# Lipo_Rider_Plus.net
KiCad netlist of a schematic drawn in EAGLE
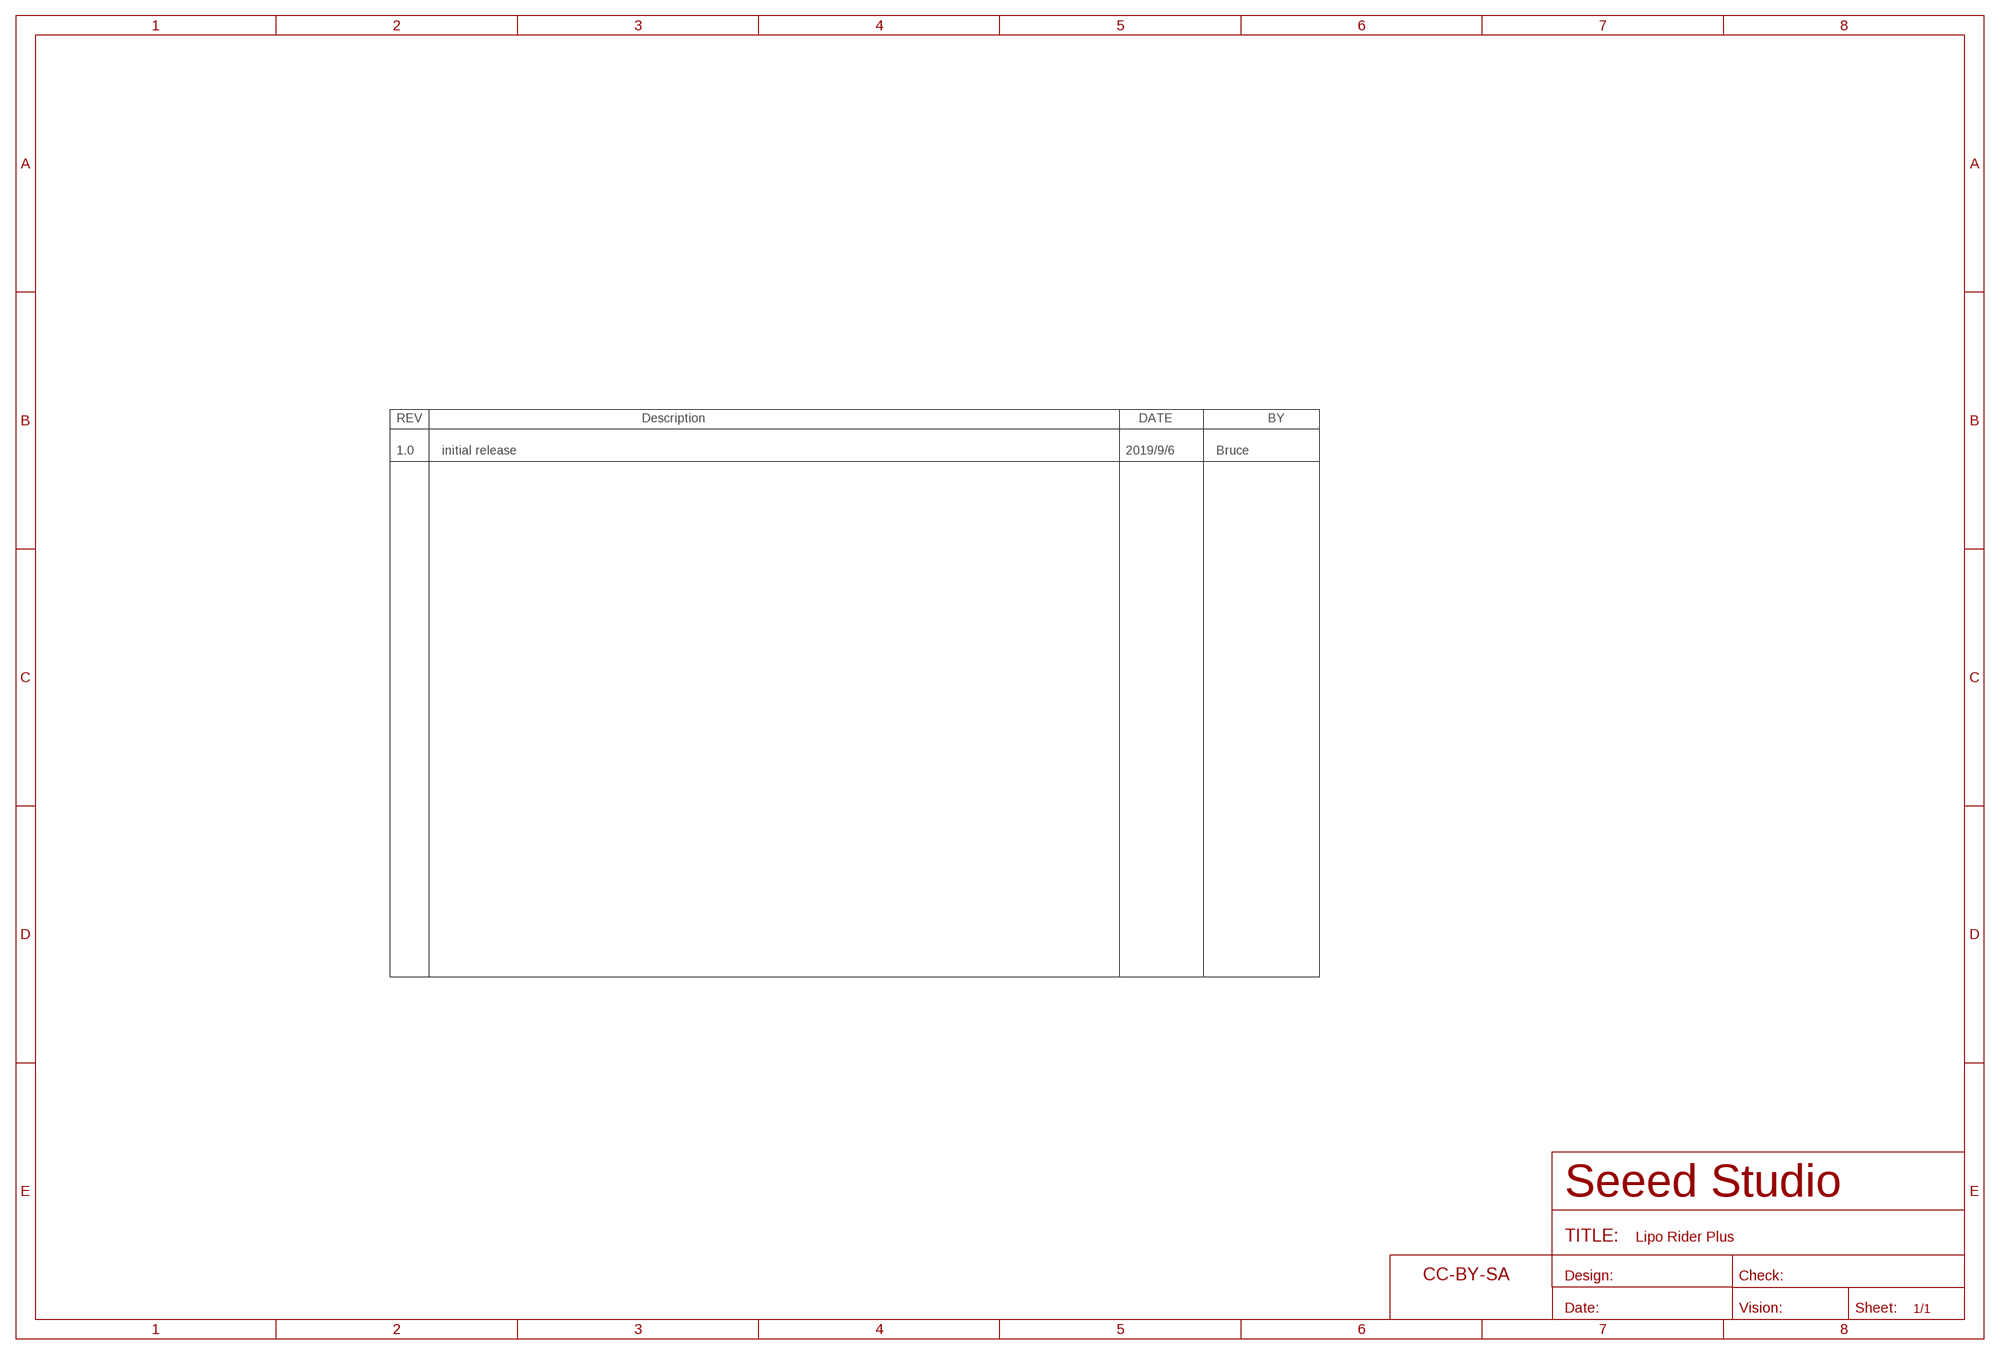
[diagram p0: schematic, sheet 1, part 1 of 2]
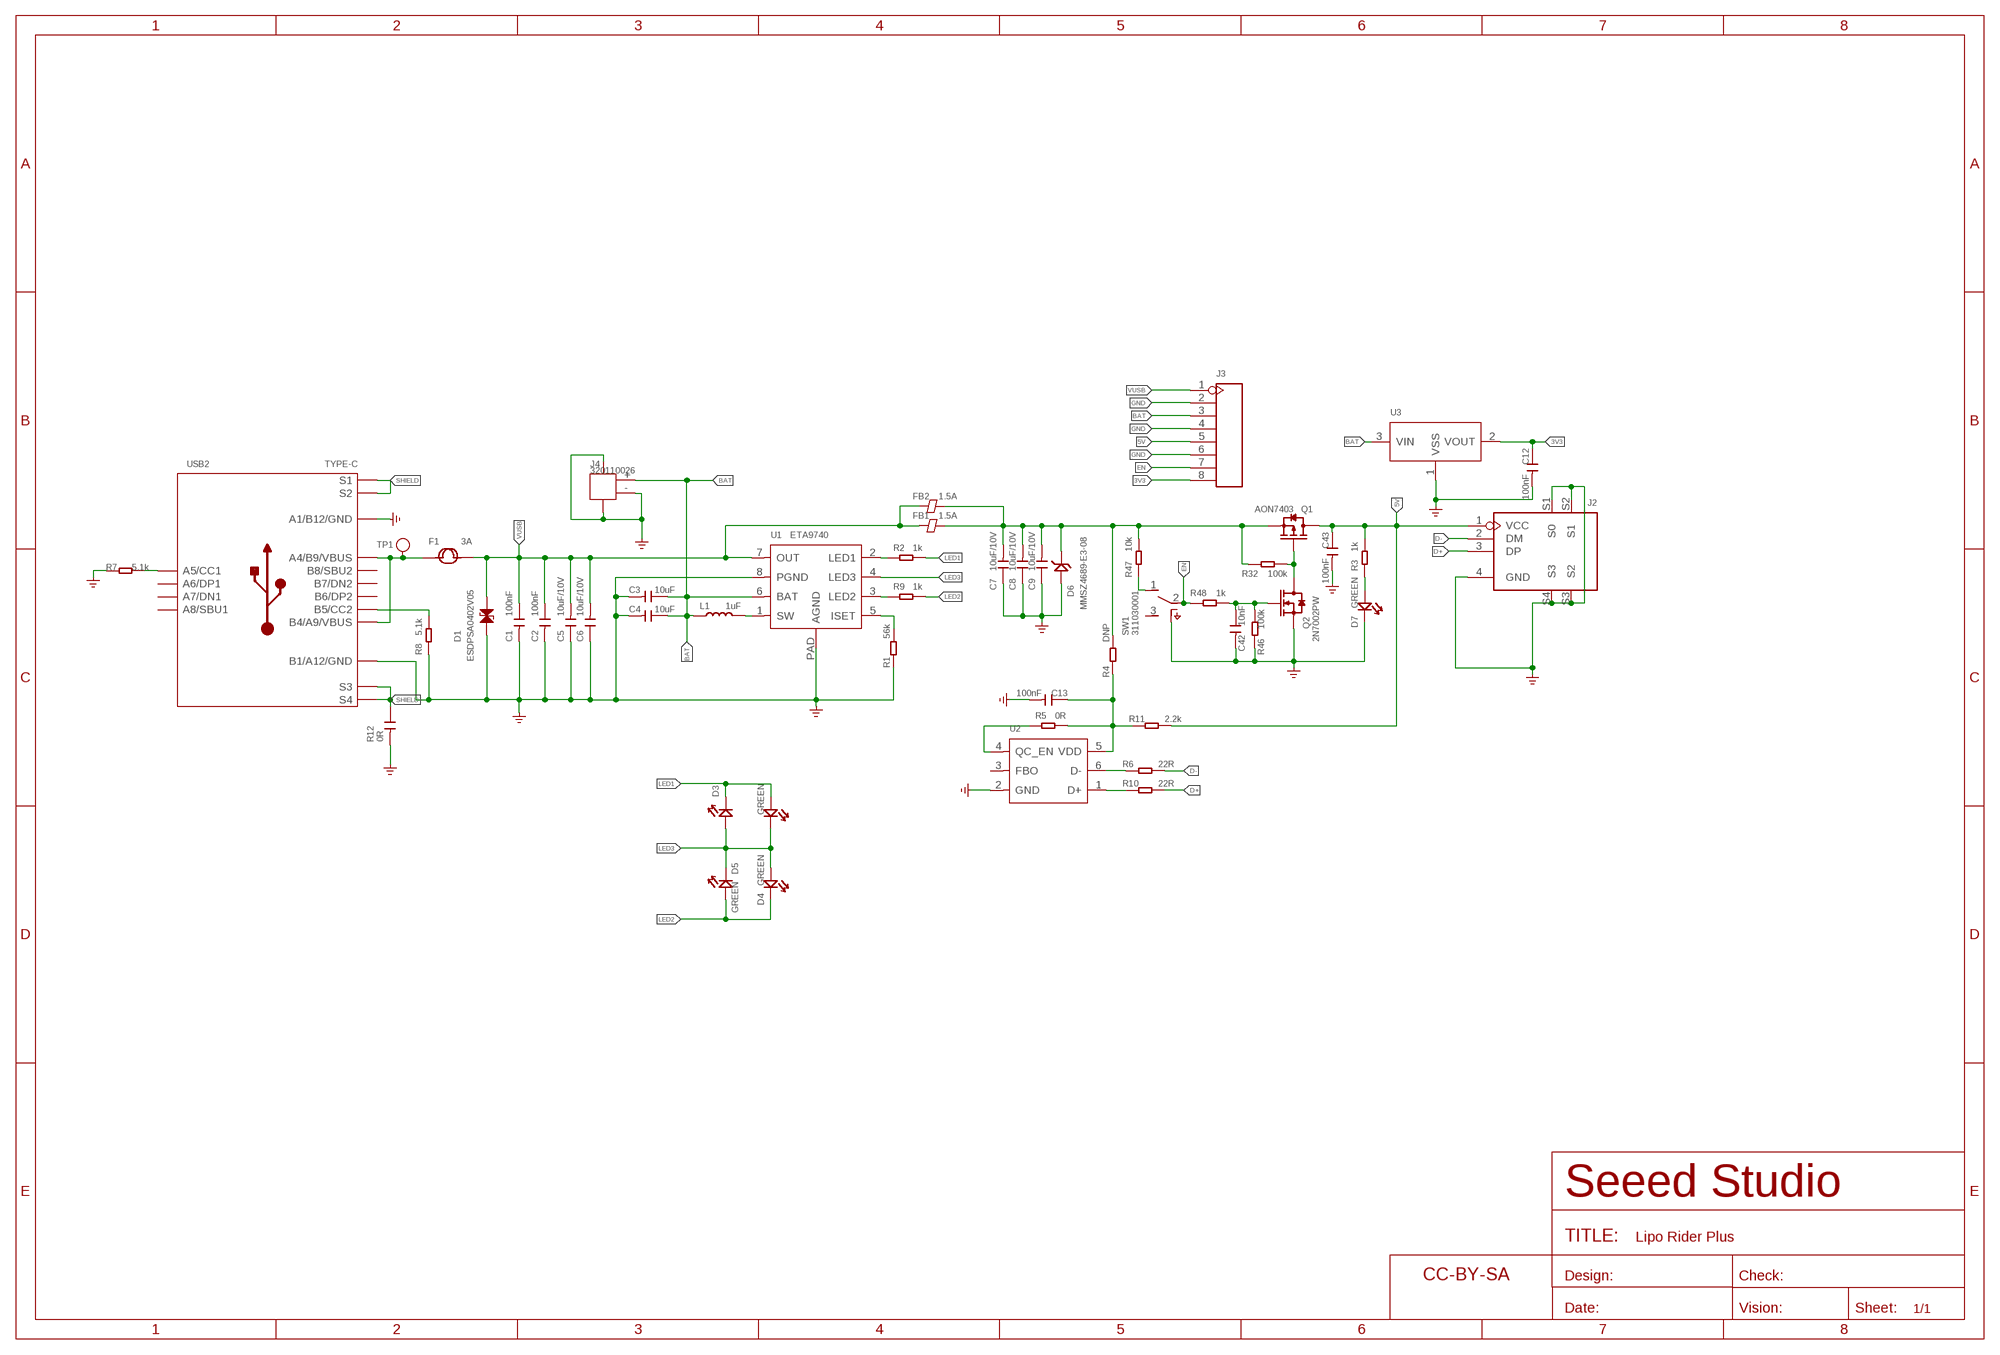
[diagram p1: schematic, sheet 1, part 2 of 2]

(export (version "E")
  (design (tool "Eeschema 10.0.6"))
  (components
    (comp (ref "C1")
      (value "100nF")
      (footprint "eagle-import:C0402")
      (libsource (lib "eagle-import") (part "CAP-0402"))
    )
    (comp (ref "C2")
      (value "100nF")
      (footprint "eagle-import:C0402")
      (libsource (lib "eagle-import") (part "CAP-0402"))
    )
    (comp (ref "C3")
      (value "10uF")
      (footprint "eagle-import:C0603")
      (libsource (lib "eagle-import") (part "CAP-0603"))
    )
    (comp (ref "C4")
      (value "10uF")
      (footprint "eagle-import:C0603")
      (libsource (lib "eagle-import") (part "CAP-0603"))
    )
    (comp (ref "C5")
      (value "10uF/10V")
      (footprint "eagle-import:C0805")
      (libsource (lib "eagle-import") (part "CAP-0805"))
    )
    (comp (ref "C6")
      (value "10uF/10V")
      (footprint "eagle-import:C0805")
      (libsource (lib "eagle-import") (part "CAP-0805"))
    )
    (comp (ref "C7")
      (value "10uF/10V")
      (footprint "eagle-import:C0805")
      (libsource (lib "eagle-import") (part "CAP-0805"))
    )
    (comp (ref "C8")
      (value "10uF/10V")
      (footprint "eagle-import:C0805")
      (libsource (lib "eagle-import") (part "CAP-0805"))
    )
    (comp (ref "C9")
      (value "10uF/10V")
      (footprint "eagle-import:C0805")
      (libsource (lib "eagle-import") (part "CAP-0805"))
    )
    (comp (ref "C12")
      (value "100nF")
      (footprint "eagle-import:C0402")
      (libsource (lib "eagle-import") (part "CAP-0402"))
    )
    (comp (ref "C13")
      (value "100nF")
      (footprint "eagle-import:C0402")
      (libsource (lib "eagle-import") (part "CAP-0402"))
    )
    (comp (ref "C42")
      (value "10nF")
      (footprint "eagle-import:C0402")
      (libsource (lib "eagle-import") (part "CAP-0402"))
    )
    (comp (ref "C43")
      (value "100nF")
      (footprint "eagle-import:C0402")
      (libsource (lib "eagle-import") (part "CAP-0402"))
    )
    (comp (ref "D1")
      (value "ESDPSA0402V05")
      (footprint "eagle-import:ESD-0402")
      (libsource (lib "eagle-import") (part "D-ESD-2P-DOUBLE-0402"))
    )
    (comp (ref "D2")
      (value "GREEN")
      (footprint "eagle-import:LED-0402")
      (libsource (lib "eagle-import") (part "LED-0402"))
    )
    (comp (ref "D3")
      (value "GREEN")
      (footprint "eagle-import:LED-0402")
      (libsource (lib "eagle-import") (part "LED-0402"))
    )
    (comp (ref "D4")
      (value "GREEN")
      (footprint "eagle-import:LED-0402")
      (libsource (lib "eagle-import") (part "LED-0402"))
    )
    (comp (ref "D5")
      (value "GREEN")
      (footprint "eagle-import:LED-0402")
      (libsource (lib "eagle-import") (part "LED-0402"))
    )
    (comp (ref "D6")
      (value "MMSZ4689-E3-08")
      (footprint "eagle-import:SOD-123")
      (libsource (lib "eagle-import") (part "D-ZENER-2P-304030008"))
    )
    (comp (ref "D7")
      (value "GREEN")
      (footprint "eagle-import:LED-0402")
      (libsource (lib "eagle-import") (part "LED-0402"))
    )
    (comp (ref "F1")
      (value "3A")
      (footprint "eagle-import:F1812")
      (libsource (lib "eagle-import") (part "FUSE'1812'"))
    )
    (comp (ref "FB1")
      (value "1.5A")
      (footprint "eagle-import:F0805")
      (libsource (lib "eagle-import") (part "FERRITE-BEAD-0805"))
    )
    (comp (ref "FB2")
      (value "1.5A")
      (footprint "eagle-import:F0805")
      (libsource (lib "eagle-import") (part "FERRITE-BEAD-0805"))
    )
    (comp (ref "FR1")
      (value "SEEEDSTUDIO-OPEN-SCH-FRAME-BIG")
      (footprint "eagle-import:SEEEDSTUDIO-PCB-FRAME")
      (libsource (lib "eagle-import") (part "SEEEDSTUDIO-OPEN-SCH-FRAME-BIG"))
    )
    (comp (ref "FR2")
      (value "SEEEDSTUDIO-OPEN-SCH-FRAME-BIG")
      (footprint "eagle-import:SEEEDSTUDIO-PCB-FRAME")
      (libsource (lib "eagle-import") (part "SEEEDSTUDIO-OPEN-SCH-FRAME-BIG"))
    )
    (comp (ref "J2")
      (value "USB4+4P-SMD+DIP")
      (footprint "eagle-import:USB4+4P-2.0-14.6X10.6X5.72MM")
      (libsource (lib "eagle-import") (part "USB4+4P-SMD+DIP"))
    )
    (comp (ref "J3")
      (value "HEADER-8P-65/35MIL")
      (footprint "eagle-import:H8-2.54-C65D35MIL")
      (libsource (lib "eagle-import") (part "HEADER-8P-65/35MIL"))
    )
    (comp (ref "J4")
      (value "320110026")
      (footprint "eagle-import:HW2-SMD-2.0-90D")
      (libsource (lib "eagle-import") (part "JST-2P-SMD'2.0'"))
    )
    (comp (ref "L1")
      (value "1uF")
      (footprint "eagle-import:L4.4X3.0MM")
      (libsource (lib "eagle-import") (part "INDUCTOR-4430"))
    )
    (comp (ref "Q1")
      (value "AON7403")
      (footprint "eagle-import:DFN8P-0.65-3X3X0.8MM")
      (libsource (lib "eagle-import") (part "MOSFET-P-AON7403"))
    )
    (comp (ref "Q2")
      (value "2N7002PW")
      (footprint "eagle-import:SOT-323")
      (libsource (lib "eagle-import") (part "MOSFET-N'SI1304BDL'"))
    )
    (comp (ref "R1")
      (value "56k")
      (footprint "eagle-import:R0402")
      (libsource (lib "eagle-import") (part "RES-0402"))
    )
    (comp (ref "R2")
      (value "1k")
      (footprint "eagle-import:R0402")
      (libsource (lib "eagle-import") (part "RES-0402"))
    )
    (comp (ref "R3")
      (value "1k")
      (footprint "eagle-import:R0402")
      (libsource (lib "eagle-import") (part "RES-0402"))
    )
    (comp (ref "R4")
      (value "DNP")
      (footprint "eagle-import:R0402")
      (libsource (lib "eagle-import") (part "RES-0402"))
    )
    (comp (ref "R5")
      (value "0R")
      (footprint "eagle-import:R0402")
      (libsource (lib "eagle-import") (part "RES-0402"))
    )
    (comp (ref "R6")
      (value "22R")
      (footprint "eagle-import:R0402")
      (libsource (lib "eagle-import") (part "RES-0402"))
    )
    (comp (ref "R7")
      (value "5.1k")
      (footprint "eagle-import:R0402")
      (libsource (lib "eagle-import") (part "RES-0402"))
    )
    (comp (ref "R8")
      (value "5.1k")
      (footprint "eagle-import:R0402")
      (libsource (lib "eagle-import") (part "RES-0402"))
    )
    (comp (ref "R9")
      (value "1k")
      (footprint "eagle-import:R0402")
      (libsource (lib "eagle-import") (part "RES-0402"))
    )
    (comp (ref "R10")
      (value "22R")
      (footprint "eagle-import:R0402")
      (libsource (lib "eagle-import") (part "RES-0402"))
    )
    (comp (ref "R11")
      (value "2.2k")
      (footprint "eagle-import:R0402")
      (libsource (lib "eagle-import") (part "RES-0402"))
    )
    (comp (ref "R12")
      (value "0R")
      (footprint "eagle-import:C0402")
      (libsource (lib "eagle-import") (part "CAP-0402"))
    )
    (comp (ref "R32")
      (value "100k")
      (footprint "eagle-import:R0402")
      (libsource (lib "eagle-import") (part "RES-0402"))
    )
    (comp (ref "R46")
      (value "100k")
      (footprint "eagle-import:R0402")
      (libsource (lib "eagle-import") (part "RES-0402"))
    )
    (comp (ref "R47")
      (value "10k")
      (footprint "eagle-import:R0402")
      (libsource (lib "eagle-import") (part "RES-0402"))
    )
    (comp (ref "R48")
      (value "1k")
      (footprint "eagle-import:R0402")
      (libsource (lib "eagle-import") (part "RES-0402"))
    )
    (comp (ref "SW1")
      (value "311030001")
      (footprint "eagle-import:SW7-SMD-L6.7X2.7X3.2MM")
      (libsource (lib "eagle-import") (part "SWITCH-3+4P-311030001"))
    )
    (comp (ref "TP1")
      (value "TEST")
      (footprint "eagle-import:TP-D45MIL")
      (fields (field (name "PARTNO") "DNP"))
      (libsource (lib "eagle-import") (part "TEST-POINT'4545'"))
    )
    (comp (ref "U1")
      (value "ETA9740")
      (footprint "eagle-import:ESOP8L-1.27-5X3.9MM")
      (libsource (lib "eagle-import") (part "PMIC-ETA9740"))
    )
    (comp (ref "U2")
      (value "CONTROLLER-FP6601Q")
      (footprint "eagle-import:SOT-23-6")
      (libsource (lib "eagle-import") (part "CONTROLLER-FP6601Q"))
    )
    (comp (ref "U3")
      (value "PMIC-XC6206PMR")
      (footprint "eagle-import:SOT-23")
      (libsource (lib "eagle-import") (part "PMIC-XC6206PMR"))
    )
    (comp (ref "USB2")
      (value "TYPE-C")
      (footprint "eagle-import:USB2.0-TYPE-C")
      (libsource (lib "eagle-import") (part "USB2.0-TYPE-C"))
    )
  )
  (nets
    (net (code "1") (name "3V3") (class "Default")
      (node (ref "C12") (pin "1") (pinfunction "1_1") (pintype "passive"))
      (node (ref "J3") (pin "8") (pinfunction "8_8") (pintype "bidirectional"))
      (node (ref "U3") (pin "2") (pinfunction "VOUT_2") (pintype "bidirectional"))
    )
    (net (code "2") (name "5V") (class "Default")
      (node (ref "C43") (pin "1") (pinfunction "1_1") (pintype "passive"))
      (node (ref "J2") (pin "1") (pinfunction "VCC_1") (pintype "bidirectional"))
      (node (ref "J3") (pin "5") (pinfunction "5_5") (pintype "bidirectional"))
      (node (ref "Q1") (pin "5") (pinfunction "D_5") (pintype "passive"))
      (node (ref "Q1") (pin "6") (pinfunction "D_6") (pintype "passive"))
      (node (ref "Q1") (pin "7") (pinfunction "D_7") (pintype "passive"))
      (node (ref "Q1") (pin "8") (pinfunction "D_8") (pintype "passive"))
      (node (ref "Q1") (pin "9") (pinfunction "D_9") (pintype "passive"))
      (node (ref "R11") (pin "2") (pinfunction "2_2") (pintype "passive"))
      (node (ref "R3") (pin "2") (pinfunction "2_2") (pintype "passive"))
    )
    (net (code "3") (name "BAT") (class "Default")
      (node (ref "C3") (pin "1") (pinfunction "1_1") (pintype "passive"))
      (node (ref "C4") (pin "1") (pinfunction "1_1") (pintype "passive"))
      (node (ref "J3") (pin "3") (pinfunction "3_3") (pintype "bidirectional"))
      (node (ref "J4") (pin "+") (pinfunction "1_+") (pintype "bidirectional"))
      (node (ref "L1") (pin "1") (pinfunction "1_1") (pintype "passive"))
      (node (ref "U1") (pin "6") (pinfunction "BAT_6") (pintype "bidirectional"))
      (node (ref "U3") (pin "3") (pinfunction "VIN_3") (pintype "bidirectional"))
    )
    (net (code "4") (name "D+") (class "Default")
      (node (ref "J2") (pin "3") (pinfunction "DP_3") (pintype "bidirectional"))
      (node (ref "R10") (pin "2") (pinfunction "2_2") (pintype "passive"))
    )
    (net (code "5") (name "D-") (class "Default")
      (node (ref "J2") (pin "2") (pinfunction "DM_2") (pintype "bidirectional"))
      (node (ref "R6") (pin "2") (pinfunction "2_2") (pintype "passive"))
    )
    (net (code "6") (name "EN") (class "Default")
      (node (ref "J3") (pin "7") (pinfunction "7_7") (pintype "bidirectional"))
      (node (ref "R48") (pin "1") (pinfunction "1_1") (pintype "passive"))
      (node (ref "SW1") (pin "2") (pinfunction "COM_2") (pintype "bidirectional"))
    )
    (net (code "7") (name "GND") (class "Default")
      (node (ref "C1") (pin "2") (pinfunction "2_2") (pintype "passive"))
      (node (ref "C12") (pin "2") (pinfunction "2_2") (pintype "passive"))
      (node (ref "C13") (pin "2") (pinfunction "2_2") (pintype "passive"))
      (node (ref "C2") (pin "2") (pinfunction "2_2") (pintype "passive"))
      (node (ref "C3") (pin "2") (pinfunction "2_2") (pintype "passive"))
      (node (ref "C4") (pin "2") (pinfunction "2_2") (pintype "passive"))
      (node (ref "C42") (pin "2") (pinfunction "2_2") (pintype "passive"))
      (node (ref "C43") (pin "2") (pinfunction "2_2") (pintype "passive"))
      (node (ref "C5") (pin "1") (pinfunction "1_1") (pintype "passive"))
      (node (ref "C6") (pin "1") (pinfunction "1_1") (pintype "passive"))
      (node (ref "C7") (pin "1") (pinfunction "1_1") (pintype "passive"))
      (node (ref "C8") (pin "1") (pinfunction "1_1") (pintype "passive"))
      (node (ref "C9") (pin "1") (pinfunction "1_1") (pintype "passive"))
      (node (ref "D1") (pin "1") (pinfunction "1_1") (pintype "bidirectional"))
      (node (ref "D6") (pin "+") (pinfunction "+_+") (pintype "bidirectional"))
      (node (ref "D7") (pin "-") (pinfunction "-_-") (pintype "passive"))
      (node (ref "J2") (pin "4") (pinfunction "GND_4") (pintype "bidirectional"))
      (node (ref "J2") (pin "S1") (pinfunction "S0_S1") (pintype "bidirectional"))
      (node (ref "J2") (pin "S2") (pinfunction "S1_S2") (pintype "bidirectional"))
      (node (ref "J2") (pin "S3") (pinfunction "S2_S3") (pintype "bidirectional"))
      (node (ref "J2") (pin "S4") (pinfunction "S3_S4") (pintype "bidirectional"))
      (node (ref "J3") (pin "2") (pinfunction "2_2") (pintype "bidirectional"))
      (node (ref "J3") (pin "4") (pinfunction "4_4") (pintype "bidirectional"))
      (node (ref "J3") (pin "6") (pinfunction "6_6") (pintype "bidirectional"))
      (node (ref "J4") (pin "-") (pinfunction "2_-") (pintype "bidirectional"))
      (node (ref "J4") (pin "3") (pinfunction "3_3") (pintype "bidirectional"))
      (node (ref "J4") (pin "4") (pinfunction "4_4") (pintype "bidirectional"))
      (node (ref "Q2") (pin "2") (pinfunction "S_2") (pintype "passive"))
      (node (ref "R1") (pin "1") (pinfunction "1_1") (pintype "passive"))
      (node (ref "R12") (pin "2") (pinfunction "2_2") (pintype "passive"))
      (node (ref "R46") (pin "1") (pinfunction "1_1") (pintype "passive"))
      (node (ref "R7") (pin "1") (pinfunction "1_1") (pintype "passive"))
      (node (ref "R8") (pin "2") (pinfunction "2_2") (pintype "passive"))
      (node (ref "SW1") (pin "SS1") (pinfunction "SS2_SS1") (pintype "bidirectional"))
      (node (ref "SW1") (pin "SS2") (pinfunction "SS2_SS2") (pintype "bidirectional"))
      (node (ref "SW1") (pin "SS3") (pinfunction "SS2_SS3") (pintype "bidirectional"))
      (node (ref "SW1") (pin "SS4") (pinfunction "SS2_SS4") (pintype "bidirectional"))
      (node (ref "U1") (pin "8") (pinfunction "PGND_8") (pintype "bidirectional"))
      (node (ref "U1") (pin "PAD") (pinfunction "AGND_PAD") (pintype "bidirectional"))
      (node (ref "U2") (pin "2") (pinfunction "GND_2") (pintype "bidirectional"))
      (node (ref "U3") (pin "1") (pinfunction "VSS_1") (pintype "bidirectional"))
      (node (ref "USB2") (pin "A1_B12") (pinfunction "A1/B12/GND_A1_B12") (pintype "bidirectional"))
      (node (ref "USB2") (pin "B1_A12") (pinfunction "B1/A12/GND_B1_A12") (pintype "bidirectional"))
    )
    (net (code "8") (name "LED1") (class "Default")
      (node (ref "D2") (pin "+") (pinfunction "+_+") (pintype "passive"))
      (node (ref "D3") (pin "-") (pinfunction "-_-") (pintype "passive"))
      (node (ref "R2") (pin "2") (pinfunction "2_2") (pintype "passive"))
    )
    (net (code "9") (name "LED2") (class "Default")
      (node (ref "D4") (pin "-") (pinfunction "-_-") (pintype "passive"))
      (node (ref "D5") (pin "+") (pinfunction "+_+") (pintype "passive"))
      (node (ref "R9") (pin "2") (pinfunction "2_2") (pintype "passive"))
    )
    (net (code "10") (name "LED3") (class "Default")
      (node (ref "D2") (pin "-") (pinfunction "-_-") (pintype "passive"))
      (node (ref "D3") (pin "+") (pinfunction "+_+") (pintype "passive"))
      (node (ref "D4") (pin "+") (pinfunction "+_+") (pintype "passive"))
      (node (ref "D5") (pin "-") (pinfunction "-_-") (pintype "passive"))
      (node (ref "U1") (pin "4") (pinfunction "LED3_4") (pintype "bidirectional"))
    )
    (net (code "11") (name "Net-(C7-Pad2)") (class "Default")
      (node (ref "C7") (pin "2") (pinfunction "2_2") (pintype "passive"))
      (node (ref "C8") (pin "2") (pinfunction "2_2") (pintype "passive"))
      (node (ref "C9") (pin "2") (pinfunction "2_2") (pintype "passive"))
      (node (ref "D6") (pin "-") (pinfunction "-_-") (pintype "bidirectional"))
      (node (ref "FB1") (pin "2") (pinfunction "2_2") (pintype "bidirectional"))
      (node (ref "FB2") (pin "2") (pinfunction "2_2") (pintype "bidirectional"))
      (node (ref "Q1") (pin "1") (pinfunction "S_1") (pintype "passive"))
      (node (ref "Q1") (pin "2") (pinfunction "S_2") (pintype "passive"))
      (node (ref "Q1") (pin "3") (pinfunction "S_3") (pintype "passive"))
      (node (ref "R32") (pin "1") (pinfunction "1_1") (pintype "passive"))
      (node (ref "R4") (pin "2") (pinfunction "2_2") (pintype "passive"))
      (node (ref "R47") (pin "2") (pinfunction "2_2") (pintype "passive"))
    )
    (net (code "12") (name "Net-(D7-Pad+)") (class "Default")
      (node (ref "D7") (pin "+") (pinfunction "+_+") (pintype "passive"))
      (node (ref "R3") (pin "1") (pinfunction "1_1") (pintype "passive"))
    )
    (net (code "13") (name "Net-(Q1-G)") (class "Default")
      (node (ref "Q1") (pin "4") (pinfunction "G_4") (pintype "passive"))
      (node (ref "Q2") (pin "3") (pinfunction "D_3") (pintype "passive"))
      (node (ref "R32") (pin "2") (pinfunction "2_2") (pintype "passive"))
    )
    (net (code "14") (name "Net-(Q2-G)") (class "Default")
      (node (ref "C42") (pin "1") (pinfunction "1_1") (pintype "passive"))
      (node (ref "Q2") (pin "1") (pinfunction "G_1") (pintype "passive"))
      (node (ref "R46") (pin "2") (pinfunction "2_2") (pintype "passive"))
      (node (ref "R48") (pin "2") (pinfunction "2_2") (pintype "passive"))
    )
    (net (code "15") (name "Net-(SW1-A)") (class "Default")
      (node (ref "R47") (pin "1") (pinfunction "1_1") (pintype "passive"))
      (node (ref "SW1") (pin "1") (pinfunction "A_1") (pintype "bidirectional"))
    )
    (net (code "16") (name "Net-(U1-ISET)") (class "Default")
      (node (ref "R1") (pin "2") (pinfunction "2_2") (pintype "passive"))
      (node (ref "U1") (pin "5") (pinfunction "ISET_5") (pintype "bidirectional"))
    )
    (net (code "17") (name "Net-(U1-LED1)") (class "Default")
      (node (ref "R2") (pin "1") (pinfunction "1_1") (pintype "passive"))
      (node (ref "U1") (pin "2") (pinfunction "LED1_2") (pintype "bidirectional"))
    )
    (net (code "18") (name "Net-(U1-LED2)") (class "Default")
      (node (ref "R9") (pin "1") (pinfunction "1_1") (pintype "passive"))
      (node (ref "U1") (pin "3") (pinfunction "LED2_3") (pintype "bidirectional"))
    )
    (net (code "19") (name "Net-(U1-SW)") (class "Default")
      (node (ref "L1") (pin "2") (pinfunction "2_2") (pintype "passive"))
      (node (ref "U1") (pin "1") (pinfunction "SW_1") (pintype "bidirectional"))
    )
    (net (code "20") (name "Net-(U2-D+)") (class "Default")
      (node (ref "R10") (pin "1") (pinfunction "1_1") (pintype "passive"))
      (node (ref "U2") (pin "1") (pinfunction "D+_1") (pintype "bidirectional"))
    )
    (net (code "21") (name "Net-(U2-D-)") (class "Default")
      (node (ref "R6") (pin "1") (pinfunction "1_1") (pintype "passive"))
      (node (ref "U2") (pin "6") (pinfunction "D-_6") (pintype "bidirectional"))
    )
    (net (code "22") (name "Net-(U2-QC_EN)") (class "Default")
      (node (ref "R5") (pin "1") (pinfunction "1_1") (pintype "passive"))
      (node (ref "U2") (pin "4") (pinfunction "QC_EN_4") (pintype "bidirectional"))
    )
    (net (code "23") (name "Net-(U2-VDD)") (class "Default")
      (node (ref "C13") (pin "1") (pinfunction "1_1") (pintype "passive"))
      (node (ref "R11") (pin "1") (pinfunction "1_1") (pintype "passive"))
      (node (ref "R4") (pin "1") (pinfunction "1_1") (pintype "passive"))
      (node (ref "R5") (pin "2") (pinfunction "2_2") (pintype "passive"))
      (node (ref "U2") (pin "5") (pinfunction "VDD_5") (pintype "bidirectional"))
    )
    (net (code "24") (name "Net-(USB2-A4{slash}B9{slash}VBUS)") (class "Default")
      (node (ref "F1") (pin "1") (pinfunction "1_1") (pintype "bidirectional"))
      (node (ref "TP1") (pin "T") (pinfunction "T_T") (pintype "bidirectional"))
      (node (ref "USB2") (pin "A4_B9") (pinfunction "A4/B9/VBUS_A4_B9") (pintype "bidirectional"))
      (node (ref "USB2") (pin "B4_A9") (pinfunction "B4/A9/VBUS_B4_A9") (pintype "bidirectional"))
    )
    (net (code "25") (name "Net-(USB2-A5{slash}CC1)") (class "Default")
      (node (ref "R7") (pin "2") (pinfunction "2_2") (pintype "passive"))
      (node (ref "USB2") (pin "A5") (pinfunction "A5/CC1_A5") (pintype "bidirectional"))
    )
    (net (code "26") (name "Net-(USB2-B5{slash}CC2)") (class "Default")
      (node (ref "R8") (pin "1") (pinfunction "1_1") (pintype "passive"))
      (node (ref "USB2") (pin "B5") (pinfunction "B5/CC2_B5") (pintype "bidirectional"))
    )
    (net (code "27") (name "SHIELD") (class "Default")
      (node (ref "R12") (pin "1") (pinfunction "1_1") (pintype "passive"))
      (node (ref "USB2") (pin "S1") (pinfunction "S1_S1") (pintype "bidirectional"))
      (node (ref "USB2") (pin "S2") (pinfunction "S2_S2") (pintype "bidirectional"))
      (node (ref "USB2") (pin "S3") (pinfunction "S3_S3") (pintype "bidirectional"))
      (node (ref "USB2") (pin "S4") (pinfunction "S4_S4") (pintype "bidirectional"))
      (node (ref "USB2") (pin "S5") (pinfunction "S1_S5") (pintype "bidirectional"))
      (node (ref "USB2") (pin "S6") (pinfunction "S2_S6") (pintype "bidirectional"))
    )
    (net (code "28") (name "VUSB") (class "Default")
      (node (ref "C1") (pin "1") (pinfunction "1_1") (pintype "passive"))
      (node (ref "C2") (pin "1") (pinfunction "1_1") (pintype "passive"))
      (node (ref "C5") (pin "2") (pinfunction "2_2") (pintype "passive"))
      (node (ref "C6") (pin "2") (pinfunction "2_2") (pintype "passive"))
      (node (ref "D1") (pin "2") (pinfunction "2_2") (pintype "bidirectional"))
      (node (ref "F1") (pin "2") (pinfunction "2_2") (pintype "bidirectional"))
      (node (ref "FB1") (pin "1") (pinfunction "1_1") (pintype "bidirectional"))
      (node (ref "FB2") (pin "1") (pinfunction "1_1") (pintype "bidirectional"))
      (node (ref "J3") (pin "1") (pinfunction "1_1") (pintype "bidirectional"))
      (node (ref "U1") (pin "7") (pinfunction "OUT_7") (pintype "bidirectional"))
    )
    (net (code "29") (name "unconnected-(SW1-B-Pad3)") (class "Default")
      (node (ref "SW1") (pin "3") (pinfunction "B_3") (pintype "bidirectional"))
    )
    (net (code "30") (name "unconnected-(U2-FBO-Pad3)") (class "Default")
      (node (ref "U2") (pin "3") (pinfunction "FBO_3") (pintype "bidirectional"))
    )
    (net (code "31") (name "unconnected-(USB2-A6{slash}DP1-PadA6)") (class "Default")
      (node (ref "USB2") (pin "A6") (pinfunction "A6/DP1_A6") (pintype "bidirectional"))
    )
    (net (code "32") (name "unconnected-(USB2-A7{slash}DN1-PadA7)") (class "Default")
      (node (ref "USB2") (pin "A7") (pinfunction "A7/DN1_A7") (pintype "bidirectional"))
    )
    (net (code "33") (name "unconnected-(USB2-A8{slash}SBU1-PadA8)") (class "Default")
      (node (ref "USB2") (pin "A8") (pinfunction "A8/SBU1_A8") (pintype "bidirectional"))
    )
    (net (code "34") (name "unconnected-(USB2-B6{slash}DP2-PadB6)") (class "Default")
      (node (ref "USB2") (pin "B6") (pinfunction "B6/DP2_B6") (pintype "bidirectional"))
    )
    (net (code "35") (name "unconnected-(USB2-B7{slash}DN2-PadB7)") (class "Default")
      (node (ref "USB2") (pin "B7") (pinfunction "B7/DN2_B7") (pintype "bidirectional"))
    )
    (net (code "36") (name "unconnected-(USB2-B8{slash}SBU2-PadB8)") (class "Default")
      (node (ref "USB2") (pin "B8") (pinfunction "B8/SBU2_B8") (pintype "bidirectional"))
    )
  )
)
